# 03_USB_TO_UART.net
KiCad netlist of a schematic drawn in Altium Designer
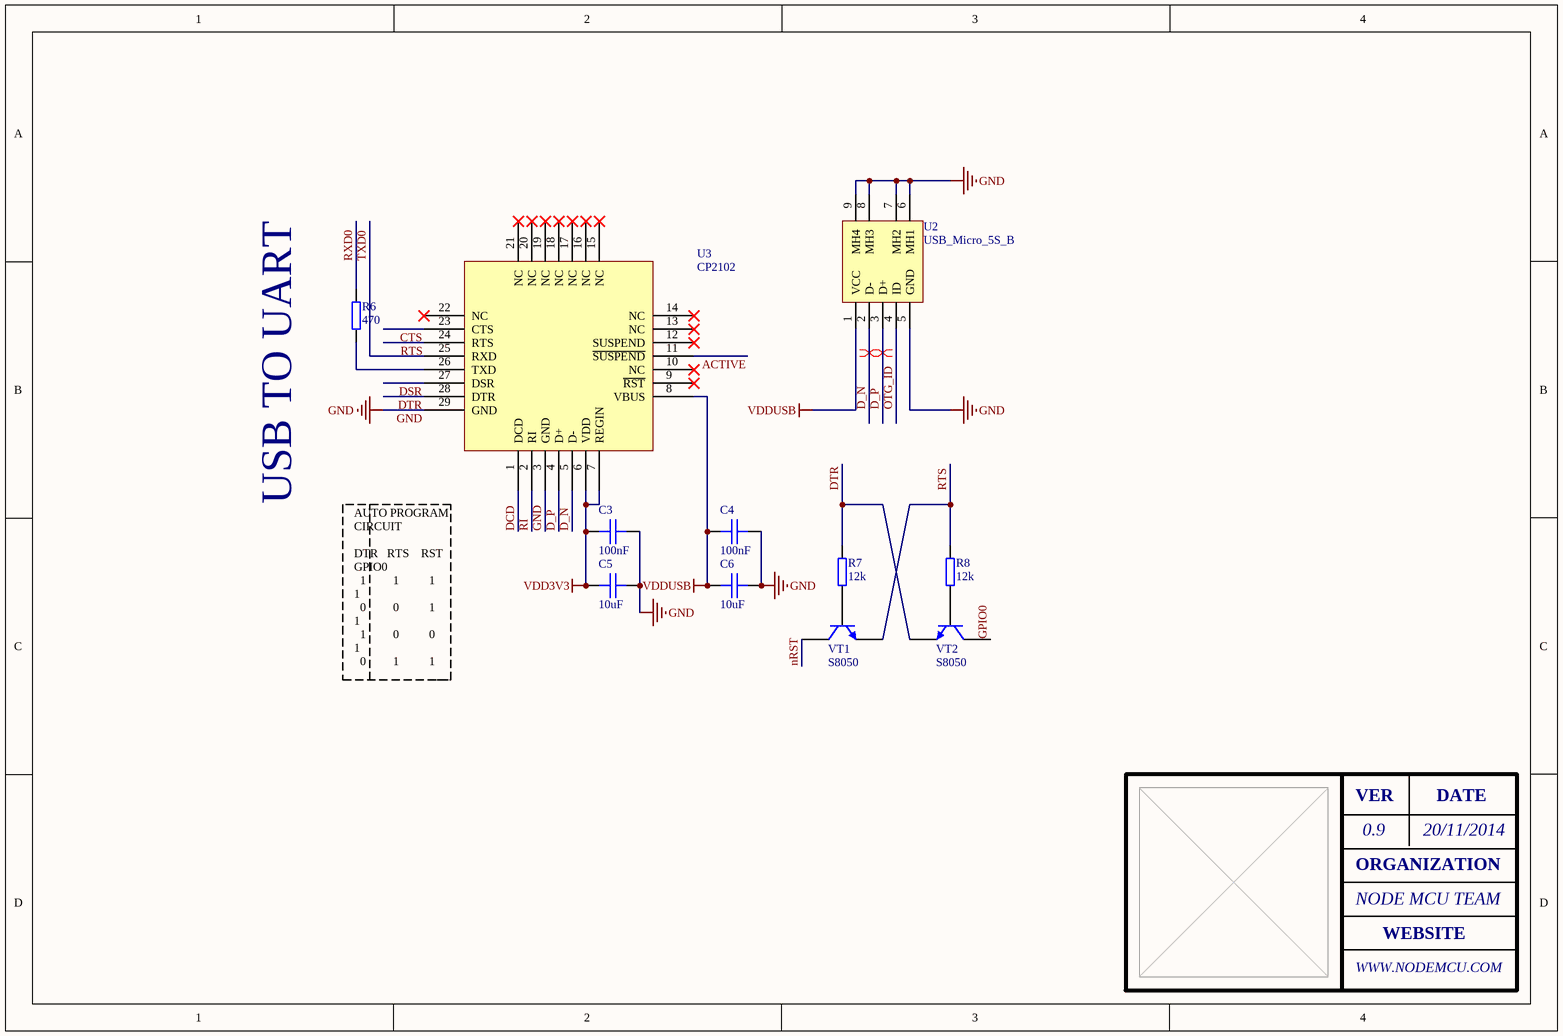
[diagram p0: 03_USB_TO_UART.SchDoc]

(export (version "E")
  (design (tool "Eeschema 10.0.6"))
  (components
    (comp (ref "C3")
      (value "100nF")
      (footprint "SMT_C_0402")
      (description "Surface mount capacitor 0402")
      (libsource (lib "Vowstar_Basic_Device") (part "SMT_C_0402"))
    )
    (comp (ref "C4")
      (value "100nF")
      (footprint "SMT_C_0402")
      (description "Surface mount capacitor 0402")
      (libsource (lib "Vowstar_Basic_Device") (part "SMT_C_0402"))
    )
    (comp (ref "C5")
      (value "10uF")
      (footprint "SMT_C_0402")
      (description "Surface mount capacitor 0402")
      (libsource (lib "Vowstar_Basic_Device") (part "SMT_C_0402"))
    )
    (comp (ref "C6")
      (value "10uF")
      (footprint "SMT_C_0402")
      (description "Surface mount capacitor 0402")
      (libsource (lib "Vowstar_Basic_Device") (part "SMT_C_0402"))
    )
    (comp (ref "R6")
      (value "470")
      (footprint "SMT_R_0402")
      (description "Surface mount resistor 0402")
      (libsource (lib "Vowstar_Basic_Device") (part "SMT_R_0402"))
    )
    (comp (ref "R7")
      (value "12k")
      (footprint "SMT_R_0402")
      (description "Surface mount resistor 0402")
      (libsource (lib "Vowstar_Basic_Device") (part "SMT_R_0402"))
    )
    (comp (ref "R8")
      (value "12k")
      (footprint "SMT_R_0402")
      (description "Surface mount resistor 0402")
      (libsource (lib "Vowstar_Basic_Device") (part "SMT_R_0402"))
    )
    (comp (ref "U2")
      (value "USB_Micro_5S_B")
      (footprint "USB_MICRO_5S_B")
      (description "USB micro female SMT with 4 fixed foot")
      (libsource (lib "Vowstar_Connector") (part "USB_Micro_5S_B"))
    )
    (comp (ref "U3")
      (value "CP2102")
      (footprint "CP2102")
      (libsource (lib "Vowstar_IC_General") (part "CP2102"))
    )
    (comp (ref "VT1")
      (value "S8050")
      (footprint "SMT_TRIODE_NPN")
      (description "Surface mount NPN transistor, package SOT-23")
      (libsource (lib "Vowstar_Basic_Device") (part "SMT_TRIODE_NPN"))
    )
    (comp (ref "VT2")
      (value "S8050")
      (footprint "SMT_TRIODE_NPN")
      (description "Surface mount NPN transistor, package SOT-23")
      (libsource (lib "Vowstar_Basic_Device") (part "SMT_TRIODE_NPN"))
    )
  )
  (nets
    (net (code "1") (name "/ACTIVE") (class "Default")
      (node (ref "U3") (pin "11") (pinfunction "~{SUSPEND}_11") (pintype "passive"))
    )
    (net (code "2") (name "/CTS") (class "Default")
      (node (ref "U3") (pin "23") (pinfunction "CTS_23") (pintype "passive"))
    )
    (net (code "3") (name "/DCD") (class "Default")
      (node (ref "U3") (pin "1") (pinfunction "DCD_1") (pintype "passive"))
    )
    (net (code "4") (name "/DSR") (class "Default")
      (node (ref "U3") (pin "27") (pinfunction "DSR_27") (pintype "passive"))
    )
    (net (code "5") (name "/DTR") (class "Default")
      (node (ref "R7") (pin "2") (pinfunction "2_2") (pintype "passive"))
      (node (ref "U3") (pin "28") (pinfunction "DTR_28") (pintype "passive"))
      (node (ref "VT2") (pin "2") (pinfunction "E_2") (pintype "passive"))
    )
    (net (code "6") (name "/D_N") (class "Default")
      (node (ref "U2") (pin "2") (pinfunction "D-_2") (pintype "passive"))
      (node (ref "U3") (pin "5") (pinfunction "D-_5") (pintype "passive"))
    )
    (net (code "7") (name "/D_P") (class "Default")
      (node (ref "U2") (pin "3") (pinfunction "D+_3") (pintype "passive"))
      (node (ref "U3") (pin "4") (pinfunction "D+_4") (pintype "passive"))
    )
    (net (code "8") (name "/GPIO0") (class "Default")
      (node (ref "VT2") (pin "3") (pinfunction "C_3") (pintype "passive"))
    )
    (net (code "9") (name "/OTG_ID") (class "Default")
      (node (ref "U2") (pin "4") (pinfunction "ID_4") (pintype "passive"))
    )
    (net (code "10") (name "/RI") (class "Default")
      (node (ref "U3") (pin "2") (pinfunction "RI_2") (pintype "passive"))
    )
    (net (code "11") (name "/RTS") (class "Default")
      (node (ref "R8") (pin "2") (pinfunction "2_2") (pintype "passive"))
      (node (ref "U3") (pin "24") (pinfunction "RTS_24") (pintype "passive"))
      (node (ref "VT1") (pin "2") (pinfunction "E_2") (pintype "passive"))
    )
    (net (code "12") (name "/RXD0") (class "Default")
      (node (ref "R6") (pin "2") (pinfunction "2_2") (pintype "passive"))
    )
    (net (code "13") (name "/TXD0") (class "Default")
      (node (ref "U3") (pin "25") (pinfunction "RXD_25") (pintype "passive"))
    )
    (net (code "14") (name "/nRST") (class "Default")
      (node (ref "VT1") (pin "3") (pinfunction "C_3") (pintype "passive"))
    )
    (net (code "15") (name "GND") (class "Default")
      (node (ref "C3") (pin "2") (pinfunction "2_2") (pintype "passive"))
      (node (ref "C4") (pin "2") (pinfunction "2_2") (pintype "passive"))
      (node (ref "C5") (pin "2") (pinfunction "2_2") (pintype "passive"))
      (node (ref "C6") (pin "2") (pinfunction "2_2") (pintype "passive"))
      (node (ref "U2") (pin "5") (pinfunction "GND_5") (pintype "passive"))
      (node (ref "U2") (pin "6") (pinfunction "MH1_6") (pintype "passive"))
      (node (ref "U2") (pin "7") (pinfunction "MH2_7") (pintype "passive"))
      (node (ref "U2") (pin "8") (pinfunction "MH3_8") (pintype "passive"))
      (node (ref "U2") (pin "9") (pinfunction "MH4_9") (pintype "passive"))
      (node (ref "U3") (pin "29") (pinfunction "GND_29") (pintype "passive"))
      (node (ref "U3") (pin "3") (pinfunction "GND_3") (pintype "passive"))
    )
    (net (code "16") (name "Net-(U3-TXD)") (class "Default")
      (node (ref "R6") (pin "1") (pinfunction "1_1") (pintype "passive"))
      (node (ref "U3") (pin "26") (pinfunction "TXD_26") (pintype "passive"))
    )
    (net (code "17") (name "Net-(VT1-B)") (class "Default")
      (node (ref "R7") (pin "1") (pinfunction "1_1") (pintype "passive"))
      (node (ref "VT1") (pin "1") (pinfunction "B_1") (pintype "passive"))
    )
    (net (code "18") (name "Net-(VT2-B)") (class "Default")
      (node (ref "R8") (pin "1") (pinfunction "1_1") (pintype "passive"))
      (node (ref "VT2") (pin "1") (pinfunction "B_1") (pintype "passive"))
    )
    (net (code "19") (name "VDD3V3") (class "Default")
      (node (ref "C3") (pin "1") (pinfunction "1_1") (pintype "passive"))
      (node (ref "C5") (pin "1") (pinfunction "1_1") (pintype "passive"))
      (node (ref "U3") (pin "6") (pinfunction "VDD_6") (pintype "passive"))
      (node (ref "U3") (pin "7") (pinfunction "REGIN_7") (pintype "passive"))
    )
    (net (code "20") (name "VDDUSB") (class "Default")
      (node (ref "C4") (pin "1") (pinfunction "1_1") (pintype "passive"))
      (node (ref "C6") (pin "1") (pinfunction "1_1") (pintype "passive"))
      (node (ref "U2") (pin "1") (pinfunction "VCC_1") (pintype "passive"))
      (node (ref "U3") (pin "8") (pinfunction "VBUS_8") (pintype "passive"))
    )
    (net (code "21") (name "unconnected-(U3-NC-Pad10)") (class "Default")
      (node (ref "U3") (pin "10") (pinfunction "NC_10") (pintype "passive+no_connect"))
    )
    (net (code "22") (name "unconnected-(U3-NC-Pad13)") (class "Default")
      (node (ref "U3") (pin "13") (pinfunction "NC_13") (pintype "passive+no_connect"))
    )
    (net (code "23") (name "unconnected-(U3-NC-Pad14)") (class "Default")
      (node (ref "U3") (pin "14") (pinfunction "NC_14") (pintype "passive+no_connect"))
    )
    (net (code "24") (name "unconnected-(U3-NC-Pad15)") (class "Default")
      (node (ref "U3") (pin "15") (pinfunction "NC_15") (pintype "passive+no_connect"))
    )
    (net (code "25") (name "unconnected-(U3-NC-Pad16)") (class "Default")
      (node (ref "U3") (pin "16") (pinfunction "NC_16") (pintype "passive+no_connect"))
    )
    (net (code "26") (name "unconnected-(U3-NC-Pad17)") (class "Default")
      (node (ref "U3") (pin "17") (pinfunction "NC_17") (pintype "passive+no_connect"))
    )
    (net (code "27") (name "unconnected-(U3-NC-Pad18)") (class "Default")
      (node (ref "U3") (pin "18") (pinfunction "NC_18") (pintype "passive+no_connect"))
    )
    (net (code "28") (name "unconnected-(U3-NC-Pad19)") (class "Default")
      (node (ref "U3") (pin "19") (pinfunction "NC_19") (pintype "passive+no_connect"))
    )
    (net (code "29") (name "unconnected-(U3-NC-Pad20)") (class "Default")
      (node (ref "U3") (pin "20") (pinfunction "NC_20") (pintype "passive+no_connect"))
    )
    (net (code "30") (name "unconnected-(U3-NC-Pad21)") (class "Default")
      (node (ref "U3") (pin "21") (pinfunction "NC_21") (pintype "passive+no_connect"))
    )
    (net (code "31") (name "unconnected-(U3-NC-Pad22)") (class "Default")
      (node (ref "U3") (pin "22") (pinfunction "NC_22") (pintype "passive+no_connect"))
    )
    (net (code "32") (name "unconnected-(U3-SUSPEND-Pad12)") (class "Default")
      (node (ref "U3") (pin "12") (pinfunction "SUSPEND_12") (pintype "passive+no_connect"))
    )
    (net (code "33") (name "unconnected-(U3-~{RST}-Pad9)") (class "Default")
      (node (ref "U3") (pin "9") (pinfunction "~{RST}_9") (pintype "passive+no_connect"))
    )
  )
)
